# LT3042_5V.net
KiCad netlist of a schematic drawn in Altium Designer
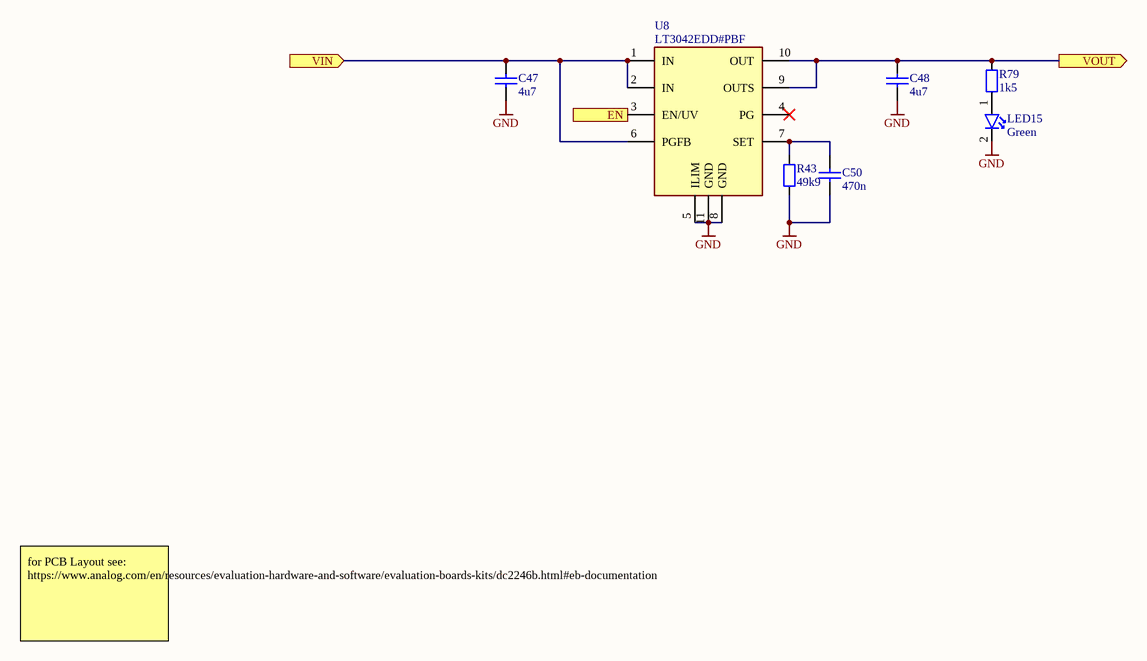
[diagram p0: LT3042_5V.SchDoc]

(export (version "E")
  (design (tool "Eeschema 10.0.6"))
  (components
    (comp (ref "C47")
      (value "4u7")
      (footprint "C_1206_3216Metric_IPC_N")
      (description "Generic MLCC with 1206 Footprint")
      (libsource (lib "database_library") (part "Capacitor_unpol"))
    )
    (comp (ref "C48")
      (value "4u7")
      (footprint "C_1206_3216Metric_IPC_N")
      (description "Generic MLCC with 1206 Footprint")
      (libsource (lib "database_library") (part "Capacitor_unpol"))
    )
    (comp (ref "C50")
      (value "470n")
      (footprint "C_0402_1005Metric_IPC_N")
      (description "Generic MLCC with 0402 Footprint")
      (libsource (lib "database_library") (part "Capacitor_unpol"))
    )
    (comp (ref "LED15")
      (value "Green")
      (footprint "LED_0603_1806Metric_IPC_N")
      (description "MLCC, Low Current, Green, 2.2V, 20mA, 0603")
      (fields
        (field (name "MANUFACTURER") "Broadcom / Avago")
        (field (name "MANUFACTURER PART NUMBER") "HSMG-C190")
      )
      (libsource (lib "database_library") (part "LED"))
    )
    (comp (ref "R43")
      (value "49k9")
      (footprint "R_0402_1005Metric_IPC_N")
      (description "Generic Chip Resistor with 0402 Footprint")
      (libsource (lib "database_library") (part "Resistor"))
    )
    (comp (ref "R79")
      (value "1k5")
      (footprint "R_0402_1005Metric_IPC_N")
      (description "Generic Chip Resistor with 0402 Footprint")
      (libsource (lib "database_library") (part "Resistor"))
    )
    (comp (ref "U8")
      (value "LT3042EDD#PBF")
      (footprint "DFN10_3x3")
      (fields (field (name "MANUFACTURER") "Analog Devices"))
      (libsource (lib "database_library") (part "LT3042-10"))
    )
  )
  (nets
    (net (code "1") (name "/EN") (class "Default")
      (node (ref "U8") (pin "3") (pinfunction "EN/UV_3") (pintype "passive"))
    )
    (net (code "2") (name "/VIN") (class "Default")
      (node (ref "C47") (pin "2") (pinfunction "2_2") (pintype "passive"))
      (node (ref "U8") (pin "1") (pinfunction "IN_1") (pintype "passive"))
      (node (ref "U8") (pin "2") (pinfunction "IN_2") (pintype "passive"))
      (node (ref "U8") (pin "6") (pinfunction "PGFB_6") (pintype "passive"))
    )
    (net (code "3") (name "/VOUT") (class "Default")
      (node (ref "C48") (pin "2") (pinfunction "2_2") (pintype "passive"))
      (node (ref "R79") (pin "1") (pinfunction "1_1") (pintype "passive"))
      (node (ref "U8") (pin "10") (pinfunction "OUT_10") (pintype "passive"))
      (node (ref "U8") (pin "9") (pinfunction "OUTS_9") (pintype "passive"))
    )
    (net (code "4") (name "GND") (class "Default")
      (node (ref "C47") (pin "1") (pinfunction "1_1") (pintype "passive"))
      (node (ref "C48") (pin "1") (pinfunction "1_1") (pintype "passive"))
      (node (ref "C50") (pin "1") (pinfunction "1_1") (pintype "passive"))
      (node (ref "LED15") (pin "2") (pinfunction "2_2") (pintype "passive"))
      (node (ref "R43") (pin "1") (pinfunction "1_1") (pintype "passive"))
      (node (ref "U8") (pin "11") (pinfunction "GND_11") (pintype "passive"))
      (node (ref "U8") (pin "5") (pinfunction "ILIM_5") (pintype "passive"))
      (node (ref "U8") (pin "8") (pinfunction "GND_8") (pintype "passive"))
    )
    (net (code "5") (name "Net-(LED15-Pad1)") (class "Default")
      (node (ref "LED15") (pin "1") (pinfunction "1_1") (pintype "passive"))
      (node (ref "R79") (pin "2") (pinfunction "2_2") (pintype "passive"))
    )
    (net (code "6") (name "Net-(U8-SET)") (class "Default")
      (node (ref "C50") (pin "2") (pinfunction "2_2") (pintype "passive"))
      (node (ref "R43") (pin "2") (pinfunction "2_2") (pintype "passive"))
      (node (ref "U8") (pin "7") (pinfunction "SET_7") (pintype "passive"))
    )
    (net (code "7") (name "unconnected-(U8-PG-Pad4)") (class "Default")
      (node (ref "U8") (pin "4") (pinfunction "PG_4") (pintype "passive+no_connect"))
    )
  )
)
